# LDR-4.net
KiCad netlist of a schematic drawn in EAGLE
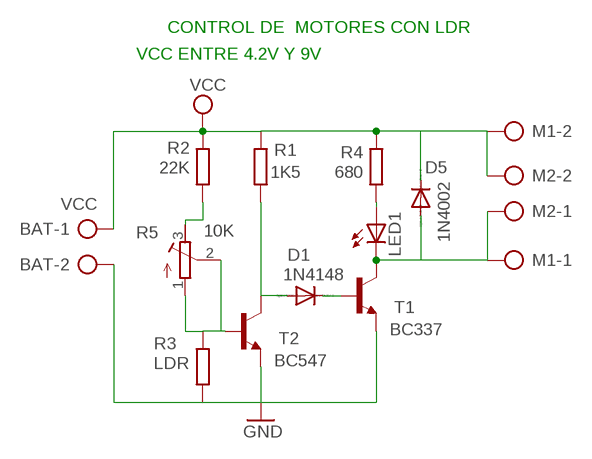
[diagram p0: schematic, sheet 1]

(export (version "E")
  (design (tool "Eeschema 10.0.6"))
  (components
    (comp (ref "BAT")
      (value "VCC")
      (footprint "eagle-import:AK500_2")
      (libsource (lib "eagle-import") (part "AK500/2"))
    )
    (comp (ref "D1")
      (value "1N4148")
      (footprint "eagle-import:DO35-7")
      (libsource (lib "eagle-import") (part "1N4148DO35-7"))
    )
    (comp (ref "D5")
      (value "1N4002")
      (footprint "eagle-import:DO41-10")
      (libsource (lib "eagle-import") (part "1N4933"))
    )
    (comp (ref "LED1")
      (value "LED3MM")
      (footprint "eagle-import:LED3MM")
      (libsource (lib "eagle-import") (part "LED3MM"))
    )
    (comp (ref "M1")
      (value "AK500/2")
      (footprint "eagle-import:AK500_2")
      (libsource (lib "eagle-import") (part "AK500/2"))
    )
    (comp (ref "M2")
      (value "AK500/2")
      (footprint "eagle-import:AK500_2")
      (libsource (lib "eagle-import") (part "AK500/2"))
    )
    (comp (ref "R1")
      (value "1K5")
      (footprint "eagle-import:0207_7")
      (libsource (lib "eagle-import") (part "R-EU_0207/7"))
    )
    (comp (ref "R2")
      (value "22K")
      (footprint "eagle-import:0207_7")
      (libsource (lib "eagle-import") (part "R-EU_0207/7"))
    )
    (comp (ref "R3")
      (value "LDR")
      (footprint "eagle-import:0204_5")
      (libsource (lib "eagle-import") (part "R-EU_0204/5"))
    )
    (comp (ref "R4")
      (value "680")
      (footprint "eagle-import:0207_7")
      (libsource (lib "eagle-import") (part "R-EU_0207/7"))
    )
    (comp (ref "R5")
      (value "10K")
      (footprint "eagle-import:RTRIM64W")
      (libsource (lib "eagle-import") (part "R-TRIMM64W"))
    )
    (comp (ref "T1")
      (value "BC337")
      (footprint "eagle-import:TO92-CBE")
      (libsource (lib "eagle-import") (part "-NPN-TO92-CBEBC337-25"))
    )
    (comp (ref "T2")
      (value "BC547")
      (footprint "eagle-import:TO92-CBE")
      (libsource (lib "eagle-import") (part "-NPN-TO92-CBEBC547"))
    )
  )
  (nets
    (net (code "1") (name "GND") (class "Default")
      (node (ref "BAT") (pin "2") (pinfunction "KL_2") (pintype "passive"))
      (node (ref "R3") (pin "1") (pinfunction "1_1") (pintype "passive"))
      (node (ref "T1") (pin "E") (pinfunction "E_E") (pintype "passive"))
      (node (ref "T2") (pin "E") (pinfunction "E_E") (pintype "passive"))
    )
    (net (code "2") (name "Net-(D1-PadA)") (class "Default")
      (node (ref "D1") (pin "A") (pinfunction "A_A") (pintype "passive"))
      (node (ref "R1") (pin "1") (pinfunction "1_1") (pintype "passive"))
      (node (ref "T2") (pin "C") (pinfunction "C_C") (pintype "passive"))
    )
    (net (code "3") (name "Net-(D1-PadC)") (class "Default")
      (node (ref "D1") (pin "C") (pinfunction "C_C") (pintype "passive"))
      (node (ref "T1") (pin "B") (pinfunction "B_B") (pintype "passive"))
    )
    (net (code "4") (name "Net-(LED1-C)") (class "Default")
      (node (ref "D5") (pin "A") (pinfunction "A_A") (pintype "passive"))
      (node (ref "LED1") (pin "K") (pinfunction "C_K") (pintype "passive"))
      (node (ref "M1") (pin "1") (pinfunction "KL_1") (pintype "passive"))
      (node (ref "M2") (pin "1") (pinfunction "KL_1") (pintype "passive"))
      (node (ref "T1") (pin "C") (pinfunction "C_C") (pintype "passive"))
    )
    (net (code "5") (name "Net-(LED1-PadA)") (class "Default")
      (node (ref "LED1") (pin "A") (pinfunction "A_A") (pintype "passive"))
      (node (ref "R4") (pin "1") (pinfunction "1_1") (pintype "passive"))
    )
    (net (code "6") (name "Net-(R5-A)") (class "Default")
      (node (ref "R3") (pin "2") (pinfunction "2_2") (pintype "passive"))
      (node (ref "R5") (pin "1") (pinfunction "A_1") (pintype "passive"))
      (node (ref "R5") (pin "2") (pinfunction "S_2") (pintype "passive"))
      (node (ref "T2") (pin "B") (pinfunction "B_B") (pintype "passive"))
    )
    (net (code "7") (name "Net-(R5-E)") (class "Default")
      (node (ref "R2") (pin "1") (pinfunction "1_1") (pintype "passive"))
      (node (ref "R5") (pin "3") (pinfunction "E_3") (pintype "passive"))
    )
    (net (code "8") (name "VCC") (class "Default")
      (node (ref "BAT") (pin "1") (pinfunction "KL_1") (pintype "passive"))
      (node (ref "D5") (pin "C") (pinfunction "C_C") (pintype "passive"))
      (node (ref "M1") (pin "2") (pinfunction "KL_2") (pintype "passive"))
      (node (ref "M2") (pin "2") (pinfunction "KL_2") (pintype "passive"))
      (node (ref "R1") (pin "2") (pinfunction "2_2") (pintype "passive"))
      (node (ref "R2") (pin "2") (pinfunction "2_2") (pintype "passive"))
      (node (ref "R4") (pin "2") (pinfunction "2_2") (pintype "passive"))
    )
  )
)
